# TC_IC2.net
KiCad netlist of a schematic drawn in Altium Designer
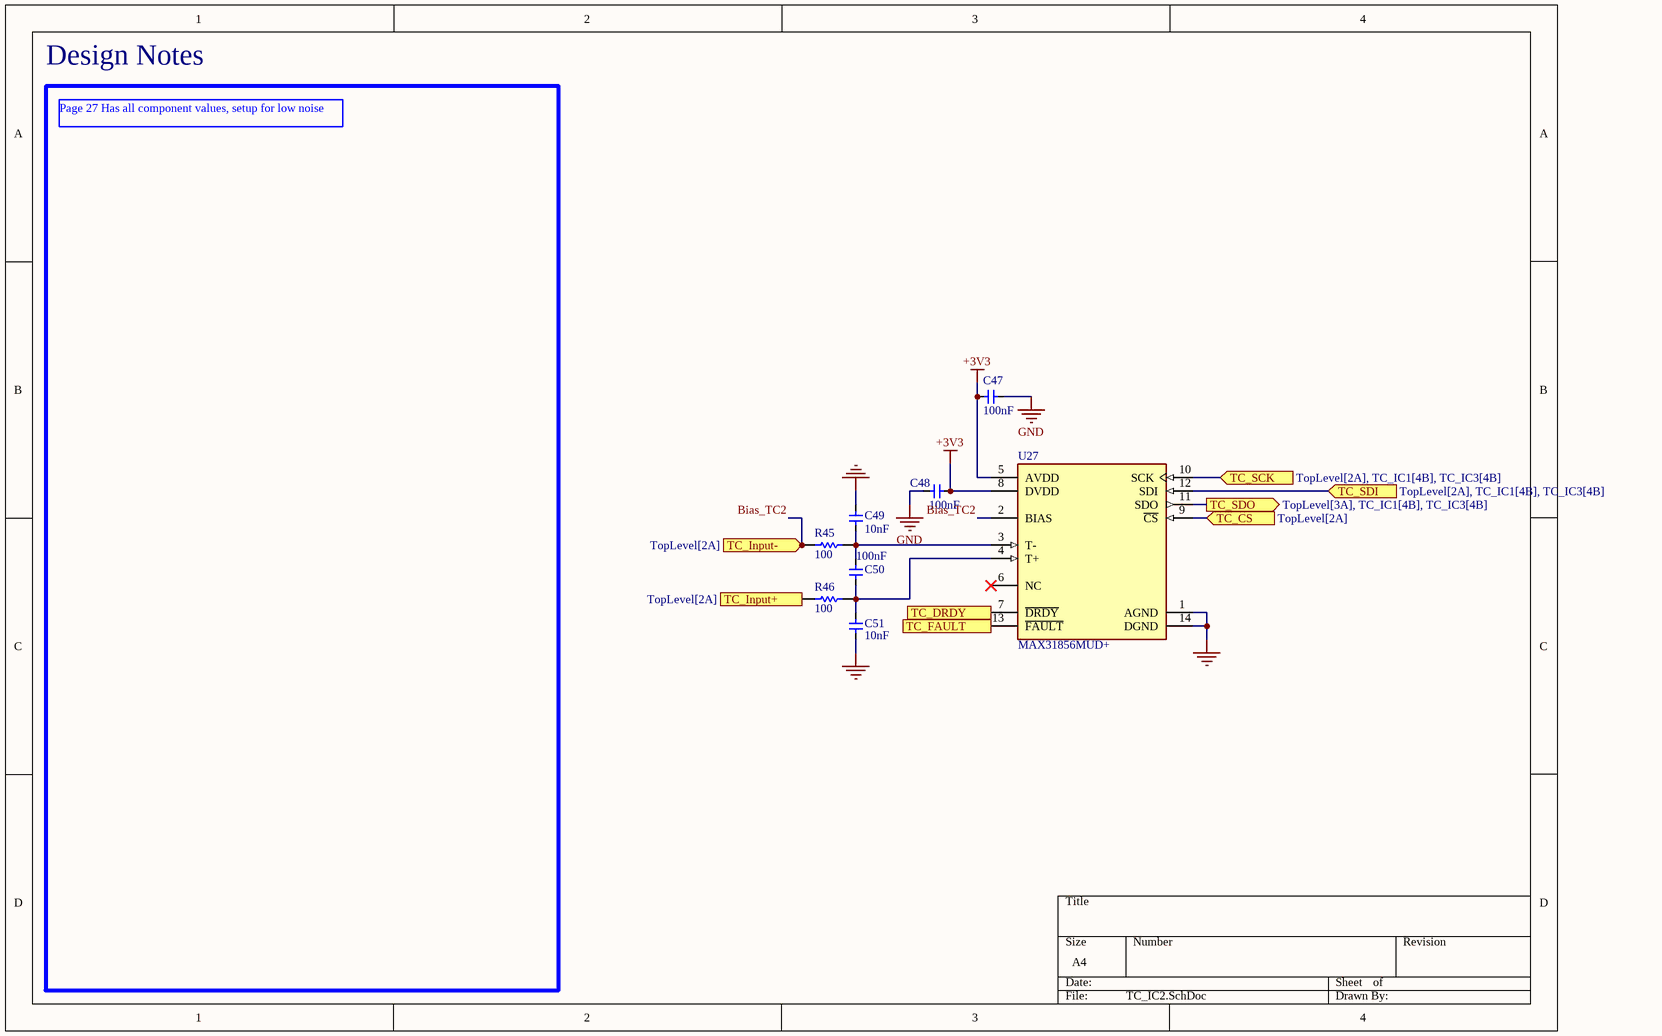
[diagram p0: TC_IC2.SchDoc]

(export (version "E")
  (design (tool "Eeschema 10.0.6"))
  (components
    (comp (ref "C47")
      (value "100nF")
      (footprint "0.1uF-FP-CGA3E-0_3-0_1-IPC_A")
      (description "CGA3E2X7R1E104K080AA CAP CER 0.1UF 25V X7R 0603")
      (fields
        (field (name "TOLERANCE") "10%")
        (field (name "MANUFACTURER") "TDK Corporation")
        (field (name "SOURCE") "PlumBay_SchLib.SchLib")
      )
      (libsource (lib "University of Calgary - SOAR") (part "100nF"))
    )
    (comp (ref "C48")
      (value "100nF")
      (footprint "0.1uF-FP-CGA3E-0_3-0_1-IPC_A")
      (description "CGA3E2X7R1E104K080AA CAP CER 0.1UF 25V X7R 0603")
      (fields
        (field (name "TOLERANCE") "10%")
        (field (name "MANUFACTURER") "TDK Corporation")
        (field (name "SOURCE") "PlumBay_SchLib.SchLib")
      )
      (libsource (lib "University of Calgary - SOAR") (part "100nF"))
    )
    (comp (ref "C49")
      (value "10nF")
      (footprint "10000pF-CAP_1608_TDK")
      (description "CAP CER 10000PF 50V X7R 0603")
      (fields
        (field (name "MANUFACTURER") "TDK Corporation")
        (field (name "TOLERANCE") "10%")
        (field (name "SOURCE") "PlumBay_SchLib.SchLib")
      )
      (libsource (lib "University of Calgary - SOAR") (part "CGA3E2X7R1H103K080AA"))
    )
    (comp (ref "C50")
      (value "100nF")
      (footprint "0.1uF-FP-CGA3E-0_3-0_1-IPC_A")
      (description "CGA3E2X7R1E104K080AA CAP CER 0.1UF 25V X7R 0603")
      (fields
        (field (name "TOLERANCE") "10%")
        (field (name "MANUFACTURER") "TDK Corporation")
        (field (name "SOURCE") "PlumBay_SchLib.SchLib")
      )
      (libsource (lib "University of Calgary - SOAR") (part "100nF"))
    )
    (comp (ref "C51")
      (value "10nF")
      (footprint "10000pF-CAP_1608_TDK")
      (description "CAP CER 10000PF 50V X7R 0603")
      (fields
        (field (name "MANUFACTURER") "TDK Corporation")
        (field (name "TOLERANCE") "10%")
        (field (name "SOURCE") "PlumBay_SchLib.SchLib")
      )
      (libsource (lib "University of Calgary - SOAR") (part "CGA3E2X7R1H103K080AA"))
    )
    (comp (ref "R45")
      (value "100")
      (footprint "RESC1608X55X30LL15T15")
      (fields
        (field (name "POWER") "100mW")
        (field (name "TOLERANCE") "1%")
        (field (name "Comment") "ERJ-3EKF1000V")
      )
      (libsource (lib "University of Calgary - SOAR") (part "RES"))
    )
    (comp (ref "R46")
      (value "100")
      (footprint "RESC1608X55X30LL15T15")
      (fields
        (field (name "POWER") "100mW")
        (field (name "TOLERANCE") "1%")
        (field (name "Comment") "ERJ-3EKF1000V")
      )
      (libsource (lib "University of Calgary - SOAR") (part "RES"))
    )
    (comp (ref "U27")
      (value "MAX31856MUD+")
      (footprint "FP-U14-2-MFG")
      (description "Analog Circuit, 1 Func, PDSO14")
      (libsource (lib "University of Calgary - SOAR") (part "746ee3d58a922cadd982a8de1b076a0"))
    )
  )
  (nets
    (net (code "1") (name "+3V3") (class "Default")
      (node (ref "C47") (pin "1") (pinfunction "1_1") (pintype "passive"))
      (node (ref "C48") (pin "1") (pinfunction "1_1") (pintype "passive"))
      (node (ref "U27") (pin "5") (pinfunction "AVDD_5") (pintype "power_in"))
      (node (ref "U27") (pin "8") (pinfunction "DVDD_8") (pintype "power_in"))
    )
    (net (code "2") (name "/Bias_TC2") (class "Default")
      (node (ref "R45") (pin "2") (pinfunction "2_2") (pintype "passive"))
      (node (ref "U27") (pin "2") (pinfunction "BIAS_2") (pintype "passive"))
    )
    (net (code "3") (name "/TC_CS") (class "Default")
      (node (ref "U27") (pin "9") (pinfunction "~{CS}_9") (pintype "input"))
    )
    (net (code "4") (name "/TC_DRDY") (class "Default")
      (node (ref "U27") (pin "7") (pinfunction "~{DRDY}_7") (pintype "passive"))
    )
    (net (code "5") (name "/TC_FAULT") (class "Default")
      (node (ref "U27") (pin "13") (pinfunction "~{FAULT}_13") (pintype "passive"))
    )
    (net (code "6") (name "/TC_Input+") (class "Default")
      (node (ref "R46") (pin "2") (pinfunction "2_2") (pintype "passive"))
    )
    (net (code "7") (name "/TC_SCK") (class "Default")
      (node (ref "U27") (pin "10") (pinfunction "SCK_10") (pintype "input"))
    )
    (net (code "8") (name "/TC_SDI") (class "Default")
      (node (ref "U27") (pin "12") (pinfunction "SDI_12") (pintype "input"))
    )
    (net (code "9") (name "/TC_SDO") (class "Default")
      (node (ref "U27") (pin "11") (pinfunction "SDO_11") (pintype "output"))
    )
    (net (code "10") (name "GND") (class "Default")
      (node (ref "C47") (pin "2") (pinfunction "2_2") (pintype "passive"))
      (node (ref "C48") (pin "2") (pinfunction "2_2") (pintype "passive"))
      (node (ref "C49") (pin "1") (pinfunction "1_1") (pintype "passive"))
      (node (ref "C51") (pin "1") (pinfunction "1_1") (pintype "passive"))
      (node (ref "U27") (pin "1") (pinfunction "AGND_1") (pintype "power_in"))
      (node (ref "U27") (pin "14") (pinfunction "DGND_14") (pintype "power_in"))
    )
    (net (code "11") (name "Net-(U27-T+)") (class "Default")
      (node (ref "C50") (pin "1") (pinfunction "1_1") (pintype "passive"))
      (node (ref "C51") (pin "2") (pinfunction "2_2") (pintype "passive"))
      (node (ref "R46") (pin "1") (pinfunction "1_1") (pintype "passive"))
      (node (ref "U27") (pin "4") (pinfunction "T+_4") (pintype "input"))
    )
    (net (code "12") (name "Net-(U27-T-)") (class "Default")
      (node (ref "C49") (pin "2") (pinfunction "2_2") (pintype "passive"))
      (node (ref "C50") (pin "2") (pinfunction "2_2") (pintype "passive"))
      (node (ref "R45") (pin "1") (pinfunction "1_1") (pintype "passive"))
      (node (ref "U27") (pin "3") (pinfunction "T-_3") (pintype "input"))
    )
    (net (code "13") (name "unconnected-(U27-NC-Pad6)") (class "Default")
      (node (ref "U27") (pin "6") (pinfunction "NC_6") (pintype "passive+no_connect"))
    )
  )
)
